# nicie_-_6.net
KiCad netlist of a schematic drawn in EAGLE
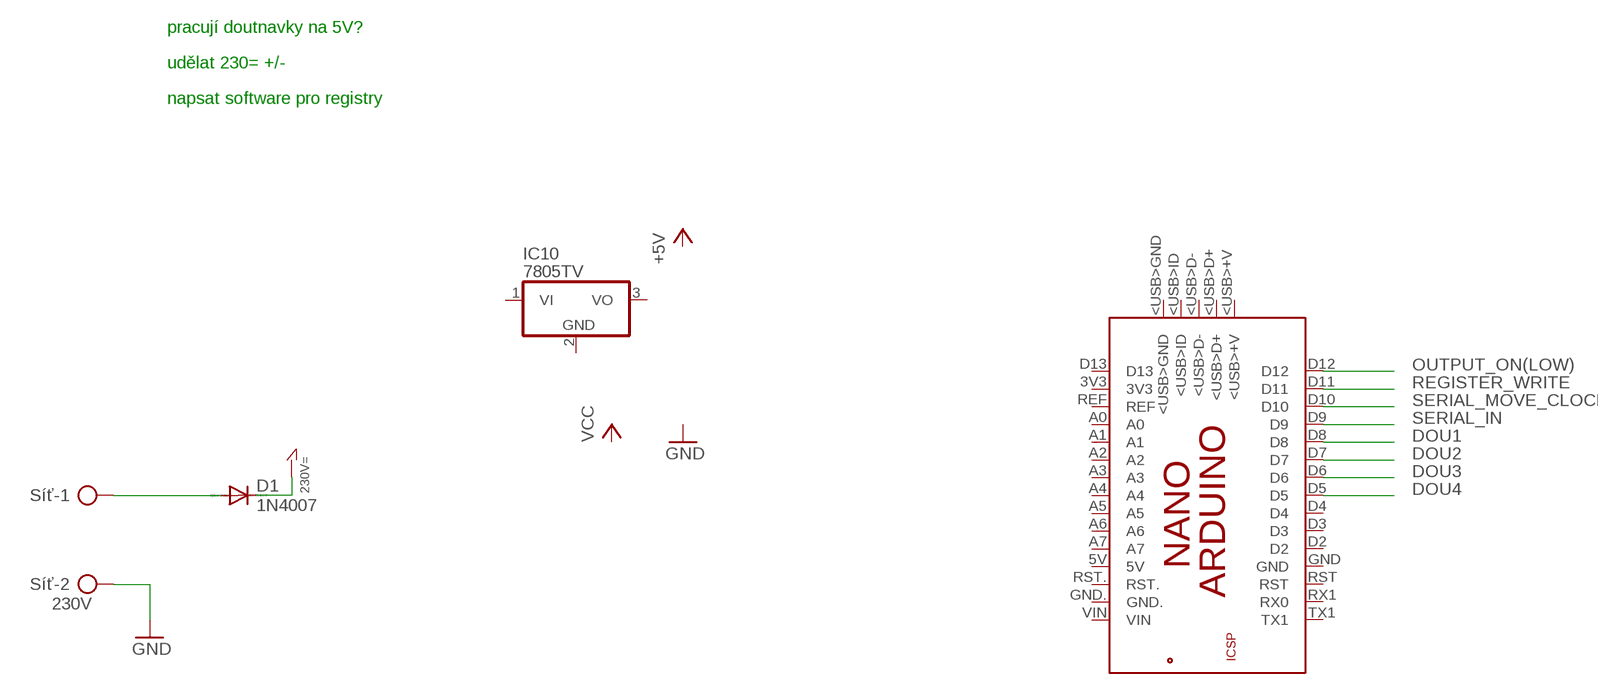
[diagram p0: schematic, sheet 1, part 1 of 2]
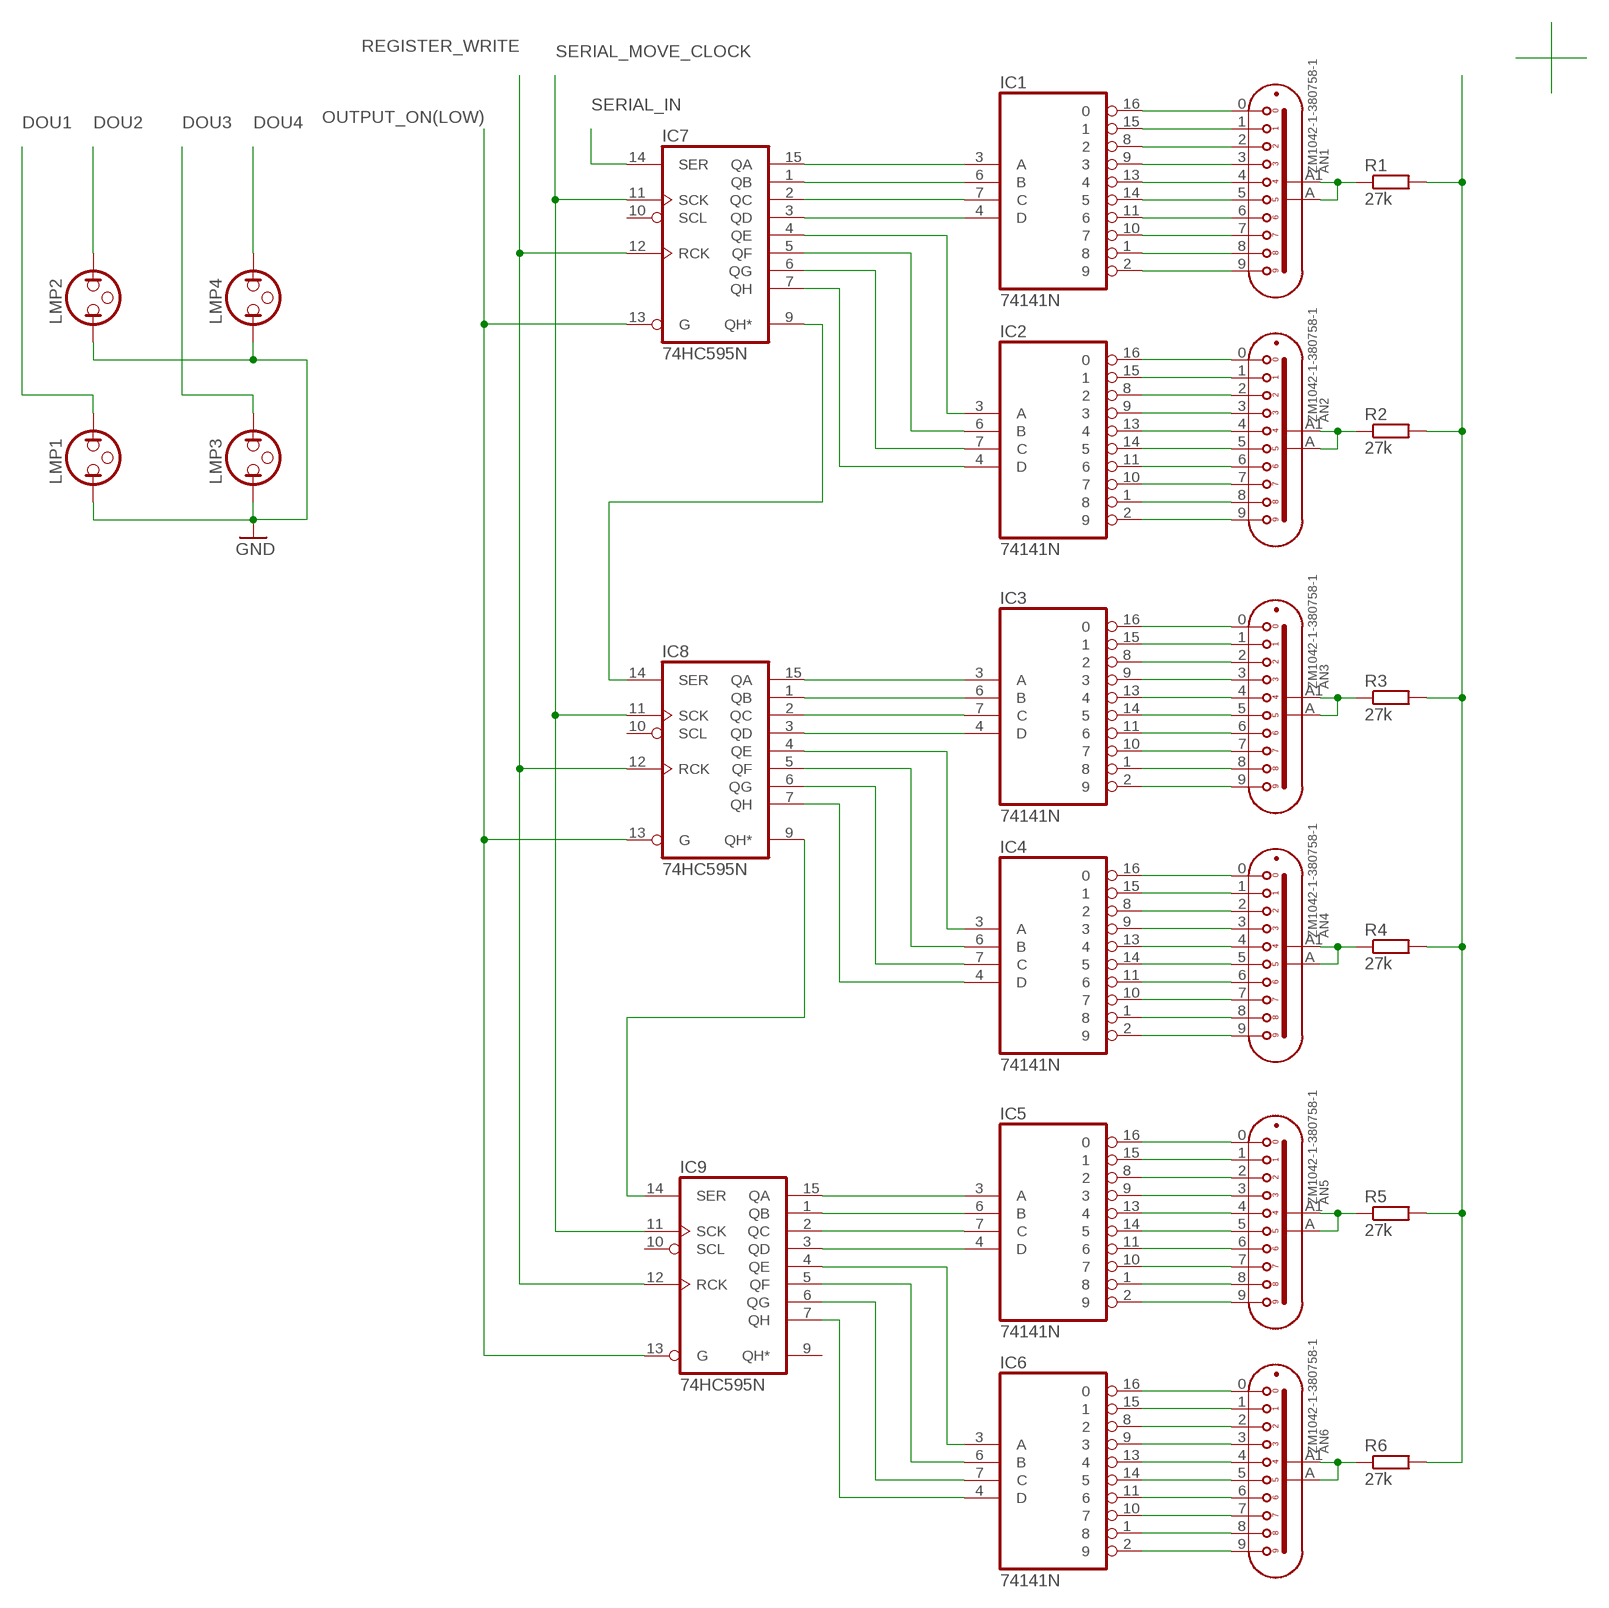
[diagram p1: schematic, sheet 1, part 2 of 2]

(export (version "E")
  (design (tool "Eeschema 10.0.6"))
  (components
    (comp (ref "AN1")
      (value "ZM1042-1-380758-1")
      (footprint "eagle-import:ZM1042-AMP")
      (libsource (lib "eagle-import") (part "ZM1042-1-380758-1"))
    )
    (comp (ref "AN2")
      (value "ZM1042-1-380758-1")
      (footprint "eagle-import:ZM1042-AMP")
      (libsource (lib "eagle-import") (part "ZM1042-1-380758-1"))
    )
    (comp (ref "AN3")
      (value "ZM1042-1-380758-1")
      (footprint "eagle-import:ZM1042-AMP")
      (libsource (lib "eagle-import") (part "ZM1042-1-380758-1"))
    )
    (comp (ref "AN4")
      (value "ZM1042-1-380758-1")
      (footprint "eagle-import:ZM1042-AMP")
      (libsource (lib "eagle-import") (part "ZM1042-1-380758-1"))
    )
    (comp (ref "AN5")
      (value "ZM1042-1-380758-1")
      (footprint "eagle-import:ZM1042-AMP")
      (libsource (lib "eagle-import") (part "ZM1042-1-380758-1"))
    )
    (comp (ref "AN6")
      (value "ZM1042-1-380758-1")
      (footprint "eagle-import:ZM1042-AMP")
      (libsource (lib "eagle-import") (part "ZM1042-1-380758-1"))
    )
    (comp (ref "D1")
      (value "1N4007")
      (footprint "eagle-import:DO41-10")
      (libsource (lib "eagle-import") (part "1N4004"))
    )
    (comp (ref "IC1")
      (value "74141N")
      (footprint "eagle-import:DIL16")
      (libsource (lib "eagle-import") (part "74141N"))
    )
    (comp (ref "IC2")
      (value "74141N")
      (footprint "eagle-import:DIL16")
      (libsource (lib "eagle-import") (part "74141N"))
    )
    (comp (ref "IC3")
      (value "74141N")
      (footprint "eagle-import:DIL16")
      (libsource (lib "eagle-import") (part "74141N"))
    )
    (comp (ref "IC4")
      (value "74141N")
      (footprint "eagle-import:DIL16")
      (libsource (lib "eagle-import") (part "74141N"))
    )
    (comp (ref "IC5")
      (value "74141N")
      (footprint "eagle-import:DIL16")
      (libsource (lib "eagle-import") (part "74141N"))
    )
    (comp (ref "IC6")
      (value "74141N")
      (footprint "eagle-import:DIL16")
      (libsource (lib "eagle-import") (part "74141N"))
    )
    (comp (ref "IC7")
      (value "74HC595N")
      (footprint "eagle-import:DIL16")
      (libsource (lib "eagle-import") (part "74595NHC"))
    )
    (comp (ref "IC8")
      (value "74HC595N")
      (footprint "eagle-import:DIL16")
      (libsource (lib "eagle-import") (part "74595NHC"))
    )
    (comp (ref "IC9")
      (value "74HC595N")
      (footprint "eagle-import:DIL16")
      (libsource (lib "eagle-import") (part "74595NHC"))
    )
    (comp (ref "IC10")
      (value "7805TV")
      (footprint "eagle-import:TO220V")
      (libsource (lib "eagle-import") (part "78TV05"))
    )
    (comp (ref "LMP1")
      (value "NEON")
      (footprint "eagle-import:LDH-3R")
      (libsource (lib "eagle-import") (part "NEON"))
    )
    (comp (ref "LMP2")
      (value "NEON")
      (footprint "eagle-import:LDH-3R")
      (libsource (lib "eagle-import") (part "NEON"))
    )
    (comp (ref "LMP3")
      (value "NEON")
      (footprint "eagle-import:LDH-3R")
      (libsource (lib "eagle-import") (part "NEON"))
    )
    (comp (ref "LMP4")
      (value "NEON")
      (footprint "eagle-import:LDH-3R")
      (libsource (lib "eagle-import") (part "NEON"))
    )
    (comp (ref "PCB1")
      (value "ARDUINO_NANO")
      (footprint "eagle-import:ARDUINO_NANO")
      (libsource (lib "eagle-import") (part "ARDUINO_NANO"))
    )
    (comp (ref "R1")
      (value "27k")
      (footprint "eagle-import:0309_12")
      (libsource (lib "eagle-import") (part "R-EU_0309/12"))
    )
    (comp (ref "R2")
      (value "27k")
      (footprint "eagle-import:0309_12")
      (libsource (lib "eagle-import") (part "R-EU_0309/12"))
    )
    (comp (ref "R3")
      (value "27k")
      (footprint "eagle-import:0309_12")
      (libsource (lib "eagle-import") (part "R-EU_0309/12"))
    )
    (comp (ref "R4")
      (value "27k")
      (footprint "eagle-import:0309_12")
      (libsource (lib "eagle-import") (part "R-EU_0309/12"))
    )
    (comp (ref "R5")
      (value "27k")
      (footprint "eagle-import:0309_12")
      (libsource (lib "eagle-import") (part "R-EU_0309/12"))
    )
    (comp (ref "R6")
      (value "27k")
      (footprint "eagle-import:0309_12")
      (libsource (lib "eagle-import") (part "R-EU_0309/12"))
    )
    (comp (ref "Síť")
      (value "230V")
      (footprint "eagle-import:AK500_2")
      (libsource (lib "eagle-import") (part "AK500/2"))
    )
  )
  (nets
    (net (code "2") (name "/DOU1") (class "Default")
      (node (ref "LMP1") (pin "2") (pinfunction "2_2") (pintype "passive"))
      (node (ref "PCB1") (pin "D8") (pinfunction "D8_D8") (pintype "bidirectional"))
    )
    (net (code "3") (name "/DOU2") (class "Default")
      (node (ref "LMP2") (pin "2") (pinfunction "2_2") (pintype "passive"))
      (node (ref "PCB1") (pin "D7") (pinfunction "D7_D7") (pintype "bidirectional"))
    )
    (net (code "4") (name "/DOU3") (class "Default")
      (node (ref "LMP3") (pin "2") (pinfunction "2_2") (pintype "passive"))
      (node (ref "PCB1") (pin "D6") (pinfunction "D6_D6") (pintype "bidirectional"))
    )
    (net (code "5") (name "/DOU4") (class "Default")
      (node (ref "LMP4") (pin "2") (pinfunction "2_2") (pintype "passive"))
      (node (ref "PCB1") (pin "D5") (pinfunction "D5_D5") (pintype "bidirectional"))
    )
    (net (code "6") (name "/OUTPUT_ON(LOW)") (class "Default")
      (node (ref "IC7") (pin "13") (pinfunction "G_13") (pintype "input"))
      (node (ref "IC8") (pin "13") (pinfunction "G_13") (pintype "input"))
      (node (ref "IC9") (pin "13") (pinfunction "G_13") (pintype "input"))
      (node (ref "PCB1") (pin "D12") (pinfunction "D12_D12") (pintype "bidirectional"))
    )
    (net (code "7") (name "/REGISTER_WRITE") (class "Default")
      (node (ref "IC7") (pin "12") (pinfunction "RCK_12") (pintype "input"))
      (node (ref "IC8") (pin "12") (pinfunction "RCK_12") (pintype "input"))
      (node (ref "IC9") (pin "12") (pinfunction "RCK_12") (pintype "input"))
      (node (ref "PCB1") (pin "D11") (pinfunction "D11_D11") (pintype "bidirectional"))
    )
    (net (code "8") (name "/SERIAL_IN") (class "Default")
      (node (ref "IC7") (pin "14") (pinfunction "SER_14") (pintype "input"))
      (node (ref "PCB1") (pin "D9") (pinfunction "D9_D9") (pintype "bidirectional"))
    )
    (net (code "9") (name "/SERIAL_MOVE_CLOCK") (class "Default")
      (node (ref "IC7") (pin "11") (pinfunction "SCK_11") (pintype "input"))
      (node (ref "IC8") (pin "11") (pinfunction "SCK_11") (pintype "input"))
      (node (ref "IC9") (pin "11") (pinfunction "SCK_11") (pintype "input"))
      (node (ref "PCB1") (pin "D10") (pinfunction "D10_D10") (pintype "bidirectional"))
    )
    (net (code "10") (name "230V=") (class "Default")
      (node (ref "D1") (pin "C") (pinfunction "C_C") (pintype "passive"))
    )
    (net (code "11") (name "GND") (class "Default")
      (node (ref "LMP1") (pin "1") (pinfunction "1_1") (pintype "passive"))
      (node (ref "LMP2") (pin "1") (pinfunction "1_1") (pintype "passive"))
      (node (ref "LMP3") (pin "1") (pinfunction "1_1") (pintype "passive"))
      (node (ref "LMP4") (pin "1") (pinfunction "1_1") (pintype "passive"))
      (node (ref "Síť") (pin "2") (pinfunction "KL_2") (pintype "passive"))
    )
    (net (code "12") (name "Net-(AN1-A1)") (class "Default")
      (node (ref "AN1") (pin "A") (pinfunction "A1_A") (pintype "passive"))
      (node (ref "AN1") (pin "A1") (pinfunction "A2_A1") (pintype "passive"))
      (node (ref "R1") (pin "1") (pinfunction "1_1") (pintype "passive"))
    )
    (net (code "13") (name "Net-(AN2-A1)") (class "Default")
      (node (ref "AN2") (pin "A") (pinfunction "A1_A") (pintype "passive"))
      (node (ref "AN2") (pin "A1") (pinfunction "A2_A1") (pintype "passive"))
      (node (ref "R2") (pin "1") (pinfunction "1_1") (pintype "passive"))
    )
    (net (code "14") (name "Net-(AN3-A1)") (class "Default")
      (node (ref "AN3") (pin "A") (pinfunction "A1_A") (pintype "passive"))
      (node (ref "AN3") (pin "A1") (pinfunction "A2_A1") (pintype "passive"))
      (node (ref "R3") (pin "1") (pinfunction "1_1") (pintype "passive"))
    )
    (net (code "15") (name "Net-(AN4-A1)") (class "Default")
      (node (ref "AN4") (pin "A") (pinfunction "A1_A") (pintype "passive"))
      (node (ref "AN4") (pin "A1") (pinfunction "A2_A1") (pintype "passive"))
      (node (ref "R4") (pin "1") (pinfunction "1_1") (pintype "passive"))
    )
    (net (code "16") (name "Net-(AN5-A1)") (class "Default")
      (node (ref "AN5") (pin "A") (pinfunction "A1_A") (pintype "passive"))
      (node (ref "AN5") (pin "A1") (pinfunction "A2_A1") (pintype "passive"))
      (node (ref "R5") (pin "1") (pinfunction "1_1") (pintype "passive"))
    )
    (net (code "17") (name "Net-(AN6-A1)") (class "Default")
      (node (ref "AN6") (pin "A") (pinfunction "A1_A") (pintype "passive"))
      (node (ref "AN6") (pin "A1") (pinfunction "A2_A1") (pintype "passive"))
      (node (ref "R6") (pin "1") (pinfunction "1_1") (pintype "passive"))
    )
    (net (code "18") (name "Net-(IC1A-0)") (class "Default")
      (node (ref "AN1") (pin "0") (pinfunction "0_0") (pintype "passive"))
      (node (ref "IC1") (pin "16") (pinfunction "0_16") (pintype "open_collector"))
    )
    (net (code "19") (name "Net-(IC1A-1)") (class "Default")
      (node (ref "AN1") (pin "1") (pinfunction "1_1") (pintype "passive"))
      (node (ref "IC1") (pin "15") (pinfunction "1_15") (pintype "open_collector"))
    )
    (net (code "20") (name "Net-(IC1A-2)") (class "Default")
      (node (ref "AN1") (pin "2") (pinfunction "2_2") (pintype "passive"))
      (node (ref "IC1") (pin "8") (pinfunction "2_8") (pintype "open_collector"))
    )
    (net (code "21") (name "Net-(IC1A-3)") (class "Default")
      (node (ref "AN1") (pin "3") (pinfunction "3_3") (pintype "passive"))
      (node (ref "IC1") (pin "9") (pinfunction "3_9") (pintype "open_collector"))
    )
    (net (code "22") (name "Net-(IC1A-4)") (class "Default")
      (node (ref "AN1") (pin "4") (pinfunction "4_4") (pintype "passive"))
      (node (ref "IC1") (pin "13") (pinfunction "4_13") (pintype "open_collector"))
    )
    (net (code "23") (name "Net-(IC1A-5)") (class "Default")
      (node (ref "AN1") (pin "5") (pinfunction "5_5") (pintype "passive"))
      (node (ref "IC1") (pin "14") (pinfunction "5_14") (pintype "open_collector"))
    )
    (net (code "24") (name "Net-(IC1A-6)") (class "Default")
      (node (ref "AN1") (pin "6") (pinfunction "6_6") (pintype "passive"))
      (node (ref "IC1") (pin "11") (pinfunction "6_11") (pintype "open_collector"))
    )
    (net (code "25") (name "Net-(IC1A-7)") (class "Default")
      (node (ref "AN1") (pin "7") (pinfunction "7_7") (pintype "passive"))
      (node (ref "IC1") (pin "10") (pinfunction "7_10") (pintype "open_collector"))
    )
    (net (code "26") (name "Net-(IC1A-8)") (class "Default")
      (node (ref "AN1") (pin "8") (pinfunction "8_8") (pintype "passive"))
      (node (ref "IC1") (pin "1") (pinfunction "8_1") (pintype "open_collector"))
    )
    (net (code "27") (name "Net-(IC1A-9)") (class "Default")
      (node (ref "AN1") (pin "9") (pinfunction "9_9") (pintype "passive"))
      (node (ref "IC1") (pin "2") (pinfunction "9_2") (pintype "open_collector"))
    )
    (net (code "28") (name "Net-(IC1A-A)") (class "Default")
      (node (ref "IC1") (pin "3") (pinfunction "A_3") (pintype "input"))
      (node (ref "IC7") (pin "15") (pinfunction "QA_15") (pintype "tri_state"))
    )
    (net (code "29") (name "Net-(IC1A-B)") (class "Default")
      (node (ref "IC1") (pin "6") (pinfunction "B_6") (pintype "input"))
      (node (ref "IC7") (pin "1") (pinfunction "QB_1") (pintype "tri_state"))
    )
    (net (code "30") (name "Net-(IC1A-C)") (class "Default")
      (node (ref "IC1") (pin "7") (pinfunction "C_7") (pintype "input"))
      (node (ref "IC7") (pin "2") (pinfunction "QC_2") (pintype "tri_state"))
    )
    (net (code "31") (name "Net-(IC1A-D)") (class "Default")
      (node (ref "IC1") (pin "4") (pinfunction "D_4") (pintype "input"))
      (node (ref "IC7") (pin "3") (pinfunction "QD_3") (pintype "tri_state"))
    )
    (net (code "32") (name "Net-(IC2A-0)") (class "Default")
      (node (ref "AN2") (pin "0") (pinfunction "0_0") (pintype "passive"))
      (node (ref "IC2") (pin "16") (pinfunction "0_16") (pintype "open_collector"))
    )
    (net (code "33") (name "Net-(IC2A-1)") (class "Default")
      (node (ref "AN2") (pin "1") (pinfunction "1_1") (pintype "passive"))
      (node (ref "IC2") (pin "15") (pinfunction "1_15") (pintype "open_collector"))
    )
    (net (code "34") (name "Net-(IC2A-2)") (class "Default")
      (node (ref "AN2") (pin "2") (pinfunction "2_2") (pintype "passive"))
      (node (ref "IC2") (pin "8") (pinfunction "2_8") (pintype "open_collector"))
    )
    (net (code "35") (name "Net-(IC2A-3)") (class "Default")
      (node (ref "AN2") (pin "3") (pinfunction "3_3") (pintype "passive"))
      (node (ref "IC2") (pin "9") (pinfunction "3_9") (pintype "open_collector"))
    )
    (net (code "36") (name "Net-(IC2A-4)") (class "Default")
      (node (ref "AN2") (pin "4") (pinfunction "4_4") (pintype "passive"))
      (node (ref "IC2") (pin "13") (pinfunction "4_13") (pintype "open_collector"))
    )
    (net (code "37") (name "Net-(IC2A-5)") (class "Default")
      (node (ref "AN2") (pin "5") (pinfunction "5_5") (pintype "passive"))
      (node (ref "IC2") (pin "14") (pinfunction "5_14") (pintype "open_collector"))
    )
    (net (code "38") (name "Net-(IC2A-6)") (class "Default")
      (node (ref "AN2") (pin "6") (pinfunction "6_6") (pintype "passive"))
      (node (ref "IC2") (pin "11") (pinfunction "6_11") (pintype "open_collector"))
    )
    (net (code "39") (name "Net-(IC2A-7)") (class "Default")
      (node (ref "AN2") (pin "7") (pinfunction "7_7") (pintype "passive"))
      (node (ref "IC2") (pin "10") (pinfunction "7_10") (pintype "open_collector"))
    )
    (net (code "40") (name "Net-(IC2A-8)") (class "Default")
      (node (ref "AN2") (pin "8") (pinfunction "8_8") (pintype "passive"))
      (node (ref "IC2") (pin "1") (pinfunction "8_1") (pintype "open_collector"))
    )
    (net (code "41") (name "Net-(IC2A-9)") (class "Default")
      (node (ref "AN2") (pin "9") (pinfunction "9_9") (pintype "passive"))
      (node (ref "IC2") (pin "2") (pinfunction "9_2") (pintype "open_collector"))
    )
    (net (code "42") (name "Net-(IC2A-A)") (class "Default")
      (node (ref "IC2") (pin "3") (pinfunction "A_3") (pintype "input"))
      (node (ref "IC7") (pin "4") (pinfunction "QE_4") (pintype "tri_state"))
    )
    (net (code "43") (name "Net-(IC2A-B)") (class "Default")
      (node (ref "IC2") (pin "6") (pinfunction "B_6") (pintype "input"))
      (node (ref "IC7") (pin "5") (pinfunction "QF_5") (pintype "tri_state"))
    )
    (net (code "44") (name "Net-(IC2A-C)") (class "Default")
      (node (ref "IC2") (pin "7") (pinfunction "C_7") (pintype "input"))
      (node (ref "IC7") (pin "6") (pinfunction "QG_6") (pintype "tri_state"))
    )
    (net (code "45") (name "Net-(IC2A-D)") (class "Default")
      (node (ref "IC2") (pin "4") (pinfunction "D_4") (pintype "input"))
      (node (ref "IC7") (pin "7") (pinfunction "QH_7") (pintype "tri_state"))
    )
    (net (code "46") (name "Net-(IC3A-0)") (class "Default")
      (node (ref "AN3") (pin "0") (pinfunction "0_0") (pintype "passive"))
      (node (ref "IC3") (pin "16") (pinfunction "0_16") (pintype "open_collector"))
    )
    (net (code "47") (name "Net-(IC3A-1)") (class "Default")
      (node (ref "AN3") (pin "1") (pinfunction "1_1") (pintype "passive"))
      (node (ref "IC3") (pin "15") (pinfunction "1_15") (pintype "open_collector"))
    )
    (net (code "48") (name "Net-(IC3A-2)") (class "Default")
      (node (ref "AN3") (pin "2") (pinfunction "2_2") (pintype "passive"))
      (node (ref "IC3") (pin "8") (pinfunction "2_8") (pintype "open_collector"))
    )
    (net (code "49") (name "Net-(IC3A-3)") (class "Default")
      (node (ref "AN3") (pin "3") (pinfunction "3_3") (pintype "passive"))
      (node (ref "IC3") (pin "9") (pinfunction "3_9") (pintype "open_collector"))
    )
    (net (code "50") (name "Net-(IC3A-4)") (class "Default")
      (node (ref "AN3") (pin "4") (pinfunction "4_4") (pintype "passive"))
      (node (ref "IC3") (pin "13") (pinfunction "4_13") (pintype "open_collector"))
    )
    (net (code "51") (name "Net-(IC3A-5)") (class "Default")
      (node (ref "AN3") (pin "5") (pinfunction "5_5") (pintype "passive"))
      (node (ref "IC3") (pin "14") (pinfunction "5_14") (pintype "open_collector"))
    )
    (net (code "52") (name "Net-(IC3A-6)") (class "Default")
      (node (ref "AN3") (pin "6") (pinfunction "6_6") (pintype "passive"))
      (node (ref "IC3") (pin "11") (pinfunction "6_11") (pintype "open_collector"))
    )
    (net (code "53") (name "Net-(IC3A-7)") (class "Default")
      (node (ref "AN3") (pin "7") (pinfunction "7_7") (pintype "passive"))
      (node (ref "IC3") (pin "10") (pinfunction "7_10") (pintype "open_collector"))
    )
    (net (code "54") (name "Net-(IC3A-8)") (class "Default")
      (node (ref "AN3") (pin "8") (pinfunction "8_8") (pintype "passive"))
      (node (ref "IC3") (pin "1") (pinfunction "8_1") (pintype "open_collector"))
    )
    (net (code "55") (name "Net-(IC3A-9)") (class "Default")
      (node (ref "AN3") (pin "9") (pinfunction "9_9") (pintype "passive"))
      (node (ref "IC3") (pin "2") (pinfunction "9_2") (pintype "open_collector"))
    )
    (net (code "56") (name "Net-(IC3A-A)") (class "Default")
      (node (ref "IC3") (pin "3") (pinfunction "A_3") (pintype "input"))
      (node (ref "IC8") (pin "15") (pinfunction "QA_15") (pintype "tri_state"))
    )
    (net (code "57") (name "Net-(IC3A-B)") (class "Default")
      (node (ref "IC3") (pin "6") (pinfunction "B_6") (pintype "input"))
      (node (ref "IC8") (pin "1") (pinfunction "QB_1") (pintype "tri_state"))
    )
    (net (code "58") (name "Net-(IC3A-C)") (class "Default")
      (node (ref "IC3") (pin "7") (pinfunction "C_7") (pintype "input"))
      (node (ref "IC8") (pin "2") (pinfunction "QC_2") (pintype "tri_state"))
    )
    (net (code "59") (name "Net-(IC3A-D)") (class "Default")
      (node (ref "IC3") (pin "4") (pinfunction "D_4") (pintype "input"))
      (node (ref "IC8") (pin "3") (pinfunction "QD_3") (pintype "tri_state"))
    )
    (net (code "60") (name "Net-(IC4A-0)") (class "Default")
      (node (ref "AN4") (pin "0") (pinfunction "0_0") (pintype "passive"))
      (node (ref "IC4") (pin "16") (pinfunction "0_16") (pintype "open_collector"))
    )
    (net (code "61") (name "Net-(IC4A-1)") (class "Default")
      (node (ref "AN4") (pin "1") (pinfunction "1_1") (pintype "passive"))
      (node (ref "IC4") (pin "15") (pinfunction "1_15") (pintype "open_collector"))
    )
    (net (code "62") (name "Net-(IC4A-2)") (class "Default")
      (node (ref "AN4") (pin "2") (pinfunction "2_2") (pintype "passive"))
      (node (ref "IC4") (pin "8") (pinfunction "2_8") (pintype "open_collector"))
    )
    (net (code "63") (name "Net-(IC4A-3)") (class "Default")
      (node (ref "AN4") (pin "3") (pinfunction "3_3") (pintype "passive"))
      (node (ref "IC4") (pin "9") (pinfunction "3_9") (pintype "open_collector"))
    )
    (net (code "64") (name "Net-(IC4A-4)") (class "Default")
      (node (ref "AN4") (pin "4") (pinfunction "4_4") (pintype "passive"))
      (node (ref "IC4") (pin "13") (pinfunction "4_13") (pintype "open_collector"))
    )
    (net (code "65") (name "Net-(IC4A-5)") (class "Default")
      (node (ref "AN4") (pin "5") (pinfunction "5_5") (pintype "passive"))
      (node (ref "IC4") (pin "14") (pinfunction "5_14") (pintype "open_collector"))
    )
    (net (code "66") (name "Net-(IC4A-6)") (class "Default")
      (node (ref "AN4") (pin "6") (pinfunction "6_6") (pintype "passive"))
      (node (ref "IC4") (pin "11") (pinfunction "6_11") (pintype "open_collector"))
    )
    (net (code "67") (name "Net-(IC4A-7)") (class "Default")
      (node (ref "AN4") (pin "7") (pinfunction "7_7") (pintype "passive"))
      (node (ref "IC4") (pin "10") (pinfunction "7_10") (pintype "open_collector"))
    )
    (net (code "68") (name "Net-(IC4A-8)") (class "Default")
      (node (ref "AN4") (pin "8") (pinfunction "8_8") (pintype "passive"))
      (node (ref "IC4") (pin "1") (pinfunction "8_1") (pintype "open_collector"))
    )
    (net (code "69") (name "Net-(IC4A-9)") (class "Default")
      (node (ref "AN4") (pin "9") (pinfunction "9_9") (pintype "passive"))
      (node (ref "IC4") (pin "2") (pinfunction "9_2") (pintype "open_collector"))
    )
    (net (code "70") (name "Net-(IC4A-A)") (class "Default")
      (node (ref "IC4") (pin "3") (pinfunction "A_3") (pintype "input"))
      (node (ref "IC8") (pin "4") (pinfunction "QE_4") (pintype "tri_state"))
    )
    (net (code "71") (name "Net-(IC4A-B)") (class "Default")
      (node (ref "IC4") (pin "6") (pinfunction "B_6") (pintype "input"))
      (node (ref "IC8") (pin "5") (pinfunction "QF_5") (pintype "tri_state"))
    )
    (net (code "72") (name "Net-(IC4A-C)") (class "Default")
      (node (ref "IC4") (pin "7") (pinfunction "C_7") (pintype "input"))
      (node (ref "IC8") (pin "6") (pinfunction "QG_6") (pintype "tri_state"))
    )
    (net (code "73") (name "Net-(IC4A-D)") (class "Default")
      (node (ref "IC4") (pin "4") (pinfunction "D_4") (pintype "input"))
      (node (ref "IC8") (pin "7") (pinfunction "QH_7") (pintype "tri_state"))
    )
    (net (code "74") (name "Net-(IC5A-0)") (class "Default")
      (node (ref "AN5") (pin "0") (pinfunction "0_0") (pintype "passive"))
      (node (ref "IC5") (pin "16") (pinfunction "0_16") (pintype "open_collector"))
    )
    (net (code "75") (name "Net-(IC5A-1)") (class "Default")
      (node (ref "AN5") (pin "1") (pinfunction "1_1") (pintype "passive"))
      (node (ref "IC5") (pin "15") (pinfunction "1_15") (pintype "open_collector"))
    )
    (net (code "76") (name "Net-(IC5A-2)") (class "Default")
      (node (ref "AN5") (pin "2") (pinfunction "2_2") (pintype "passive"))
      (node (ref "IC5") (pin "8") (pinfunction "2_8") (pintype "open_collector"))
    )
    (net (code "77") (name "Net-(IC5A-3)") (class "Default")
      (node (ref "AN5") (pin "3") (pinfunction "3_3") (pintype "passive"))
      (node (ref "IC5") (pin "9") (pinfunction "3_9") (pintype "open_collector"))
    )
    (net (code "78") (name "Net-(IC5A-4)") (class "Default")
      (node (ref "AN5") (pin "4") (pinfunction "4_4") (pintype "passive"))
      (node (ref "IC5") (pin "13") (pinfunction "4_13") (pintype "open_collector"))
    )
    (net (code "79") (name "Net-(IC5A-5)") (class "Default")
      (node (ref "AN5") (pin "5") (pinfunction "5_5") (pintype "passive"))
      (node (ref "IC5") (pin "14") (pinfunction "5_14") (pintype "open_collector"))
    )
    (net (code "80") (name "Net-(IC5A-6)") (class "Default")
      (node (ref "AN5") (pin "6") (pinfunction "6_6") (pintype "passive"))
      (node (ref "IC5") (pin "11") (pinfunction "6_11") (pintype "open_collector"))
    )
    (net (code "81") (name "Net-(IC5A-7)") (class "Default")
      (node (ref "AN5") (pin "7") (pinfunction "7_7") (pintype "passive"))
      (node (ref "IC5") (pin "10") (pinfunction "7_10") (pintype "open_collector"))
    )
    (net (code "82") (name "Net-(IC5A-8)") (class "Default")
      (node (ref "AN5") (pin "8") (pinfunction "8_8") (pintype "passive"))
      (node (ref "IC5") (pin "1") (pinfunction "8_1") (pintype "open_collector"))
    )
    (net (code "83") (name "Net-(IC5A-9)") (class "Default")
      (node (ref "AN5") (pin "9") (pinfunction "9_9") (pintype "passive"))
      (node (ref "IC5") (pin "2") (pinfunction "9_2") (pintype "open_collector"))
    )
    (net (code "84") (name "Net-(IC5A-A)") (class "Default")
      (node (ref "IC5") (pin "3") (pinfunction "A_3") (pintype "input"))
      (node (ref "IC9") (pin "15") (pinfunction "QA_15") (pintype "tri_state"))
    )
    (net (code "85") (name "Net-(IC5A-B)") (class "Default")
      (node (ref "IC5") (pin "6") (pinfunction "B_6") (pintype "input"))
      (node (ref "IC9") (pin "1") (pinfunction "QB_1") (pintype "tri_state"))
    )
    (net (code "86") (name "Net-(IC5A-C)") (class "Default")
      (node (ref "IC5") (pin "7") (pinfunction "C_7") (pintype "input"))
      (node (ref "IC9") (pin "2") (pinfunction "QC_2") (pintype "tri_state"))
    )
    (net (code "87") (name "Net-(IC5A-D)") (class "Default")
      (node (ref "IC5") (pin "4") (pinfunction "D_4") (pintype "input"))
      (node (ref "IC9") (pin "3") (pinfunction "QD_3") (pintype "tri_state"))
    )
    (net (code "88") (name "Net-(IC6A-0)") (class "Default")
      (node (ref "AN6") (pin "0") (pinfunction "0_0") (pintype "passive"))
      (node (ref "IC6") (pin "16") (pinfunction "0_16") (pintype "open_collector"))
    )
    (net (code "89") (name "Net-(IC6A-1)") (class "Default")
      (node (ref "AN6") (pin "1") (pinfunction "1_1") (pintype "passive"))
      (node (ref "IC6") (pin "15") (pinfunction "1_15") (pintype "open_collector"))
    )
    (net (code "90") (name "Net-(IC6A-2)") (class "Default")
      (node (ref "AN6") (pin "2") (pinfunction "2_2") (pintype "passive"))
      (node (ref "IC6") (pin "8") (pinfunction "2_8") (pintype "open_collector"))
    )
    (net (code "91") (name "Net-(IC6A-3)") (class "Default")
      (node (ref "AN6") (pin "3") (pinfunction "3_3") (pintype "passive"))
      (node (ref "IC6") (pin "9") (pinfunction "3_9") (pintype "open_collector"))
    )
    (net (code "92") (name "Net-(IC6A-4)") (class "Default")
      (node (ref "AN6") (pin "4") (pinfunction "4_4") (pintype "passive"))
      (node (ref "IC6") (pin "13") (pinfunction "4_13") (pintype "open_collector"))
    )
    (net (code "93") (name "Net-(IC6A-5)") (class "Default")
      (node (ref "AN6") (pin "5") (pinfunction "5_5") (pintype "passive"))
      (node (ref "IC6") (pin "14") (pinfunction "5_14") (pintype "open_collector"))
    )
    (net (code "94") (name "Net-(IC6A-6)") (class "Default")
      (node (ref "AN6") (pin "6") (pinfunction "6_6") (pintype "passive"))
      (node (ref "IC6") (pin "11") (pinfunction "6_11") (pintype "open_collector"))
    )
    (net (code "95") (name "Net-(IC6A-7)") (class "Default")
      (node (ref "AN6") (pin "7") (pinfunction "7_7") (pintype "passive"))
      (node (ref "IC6") (pin "10") (pinfunction "7_10") (pintype "open_collector"))
    )
    (net (code "96") (name "Net-(IC6A-8)") (class "Default")
      (node (ref "AN6") (pin "8") (pinfunction "8_8") (pintype "passive"))
      (node (ref "IC6") (pin "1") (pinfunction "8_1") (pintype "open_collector"))
    )
    (net (code "97") (name "Net-(IC6A-9)") (class "Default")
      (node (ref "AN6") (pin "9") (pinfunction "9_9") (pintype "passive"))
      (node (ref "IC6") (pin "2") (pinfunction "9_2") (pintype "open_collector"))
    )
    (net (code "98") (name "Net-(IC6A-A)") (class "Default")
      (node (ref "IC6") (pin "3") (pinfunction "A_3") (pintype "input"))
      (node (ref "IC9") (pin "4") (pinfunction "QE_4") (pintype "tri_state"))
    )
    (net (code "99") (name "Net-(IC6A-B)") (class "Default")
      (node (ref "IC6") (pin "6") (pinfunction "B_6") (pintype "input"))
      (node (ref "IC9") (pin "5") (pinfunction "QF_5") (pintype "tri_state"))
    )
    (net (code "100") (name "Net-(IC6A-C)") (class "Default")
      (node (ref "IC6") (pin "7") (pinfunction "C_7") (pintype "input"))
      (node (ref "IC9") (pin "6") (pinfunction "QG_6") (pintype "tri_state"))
    )
    (net (code "101") (name "Net-(IC6A-D)") (class "Default")
      (node (ref "IC6") (pin "4") (pinfunction "D_4") (pintype "input"))
      (node (ref "IC9") (pin "7") (pinfunction "QH_7") (pintype "tri_state"))
    )
    (net (code "102") (name "Net-(IC7A-QH*)") (class "Default")
      (node (ref "IC7") (pin "9") (pinfunction "QH*_9") (pintype "tri_state"))
      (node (ref "IC8") (pin "14") (pinfunction "SER_14") (pintype "input"))
    )
    (net (code "103") (name "Net-(IC8A-QH*)") (class "Default")
      (node (ref "IC8") (pin "9") (pinfunction "QH*_9") (pintype "tri_state"))
      (node (ref "IC9") (pin "14") (pinfunction "SER_14") (pintype "input"))
    )
    (net (code "104") (name "Net-(R1-Pad2)") (class "Default")
      (node (ref "R1") (pin "2") (pinfunction "2_2") (pintype "passive"))
      (node (ref "R2") (pin "2") (pinfunction "2_2") (pintype "passive"))
      (node (ref "R3") (pin "2") (pinfunction "2_2") (pintype "passive"))
      (node (ref "R4") (pin "2") (pinfunction "2_2") (pintype "passive"))
      (node (ref "R5") (pin "2") (pinfunction "2_2") (pintype "passive"))
      (node (ref "R6") (pin "2") (pinfunction "2_2") (pintype "passive"))
    )
    (net (code "105") (name "Net-(SíťA-KL)") (class "Default")
      (node (ref "D1") (pin "A") (pinfunction "A_A") (pintype "passive"))
      (node (ref "Síť") (pin "1") (pinfunction "KL_1") (pintype "passive"))
    )
    (net (code "107") (name "unconnected-(IC7A-SCL-Pad10)") (class "Default")
      (node (ref "IC7") (pin "10") (pinfunction "SCL_10") (pintype "input"))
    )
    (net (code "108") (name "unconnected-(IC8A-SCL-Pad10)") (class "Default")
      (node (ref "IC8") (pin "10") (pinfunction "SCL_10") (pintype "input"))
    )
    (net (code "109") (name "unconnected-(IC9A-QH*-Pad9)") (class "Default")
      (node (ref "IC9") (pin "9") (pinfunction "QH*_9") (pintype "tri_state"))
    )
    (net (code "110") (name "unconnected-(IC9A-SCL-Pad10)") (class "Default")
      (node (ref "IC9") (pin "10") (pinfunction "SCL_10") (pintype "input"))
    )
    (net (code "111") (name "unconnected-(IC10-GND-Pad2)") (class "Default")
      (node (ref "IC10") (pin "2") (pinfunction "GND_2") (pintype "passive"))
    )
    (net (code "112") (name "unconnected-(IC10-VI-Pad1)") (class "Default")
      (node (ref "IC10") (pin "1") (pinfunction "VI_1") (pintype "input"))
    )
    (net (code "113") (name "unconnected-(IC10-VO-Pad3)") (class "Default")
      (node (ref "IC10") (pin "3") (pinfunction "VO_3") (pintype "passive"))
    )
    (net (code "114") (name "unconnected-(PCB1-Pad3V3)") (class "Default")
      (node (ref "PCB1") (pin "3V3") (pinfunction "3V3_3V3") (pintype "bidirectional"))
    )
    (net (code "115") (name "unconnected-(PCB1-Pad5V)") (class "Default")
      (node (ref "PCB1") (pin "5V") (pinfunction "5V_5V") (pintype "bidirectional"))
    )
    (net (code "116") (name "unconnected-(PCB1-Pad5V.)") (class "Default")
      (node (ref "PCB1") (pin "5V.") (pinfunction "5V._5V.") (pintype "bidirectional"))
    )
    (net (code "117") (name "unconnected-(PCB1-Pad<USB>+V)") (class "Default")
      (node (ref "PCB1") (pin "<USB>+V") (pinfunction "<USB>+V_<USB>+V") (pintype "bidirectional"))
    )
    (net (code "118") (name "unconnected-(PCB1-Pad<USB>D+)") (class "Default")
      (node (ref "PCB1") (pin "<USB>D+") (pinfunction "<USB>D+_<USB>D+") (pintype "bidirectional"))
    )
    (net (code "119") (name "unconnected-(PCB1-Pad<USB>D-)") (class "Default")
      (node (ref "PCB1") (pin "<USB>D-") (pinfunction "<USB>D-_<USB>D-") (pintype "bidirectional"))
    )
    (net (code "120") (name "unconnected-(PCB1-Pad<USB>GND)") (class "Default")
      (node (ref "PCB1") (pin "<USB>GND") (pinfunction "<USB>GND_<USB>GND") (pintype "bidirectional"))
    )
    (net (code "121") (name "unconnected-(PCB1-Pad<USB>ID)") (class "Default")
      (node (ref "PCB1") (pin "<USB>ID") (pinfunction "<USB>ID_<USB>ID") (pintype "bidirectional"))
    )
    (net (code "122") (name "unconnected-(PCB1-PadA0)") (class "Default")
      (node (ref "PCB1") (pin "A0") (pinfunction "A0_A0") (pintype "bidirectional"))
    )
    (net (code "123") (name "unconnected-(PCB1-PadA1)") (class "Default")
      (node (ref "PCB1") (pin "A1") (pinfunction "A1_A1") (pintype "bidirectional"))
    )
    (net (code "124") (name "unconnected-(PCB1-PadA2)") (class "Default")
      (node (ref "PCB1") (pin "A2") (pinfunction "A2_A2") (pintype "bidirectional"))
    )
    (net (code "125") (name "unconnected-(PCB1-PadA3)") (class "Default")
      (node (ref "PCB1") (pin "A3") (pinfunction "A3_A3") (pintype "bidirectional"))
    )
    (net (code "126") (name "unconnected-(PCB1-PadA4)") (class "Default")
      (node (ref "PCB1") (pin "A4") (pinfunction "A4_A4") (pintype "bidirectional"))
    )
    (net (code "127") (name "unconnected-(PCB1-PadA5)") (class "Default")
      (node (ref "PCB1") (pin "A5") (pinfunction "A5_A5") (pintype "bidirectional"))
    )
    (net (code "128") (name "unconnected-(PCB1-PadA6)") (class "Default")
      (node (ref "PCB1") (pin "A6") (pinfunction "A6_A6") (pintype "bidirectional"))
    )
    (net (code "129") (name "unconnected-(PCB1-PadA7)") (class "Default")
      (node (ref "PCB1") (pin "A7") (pinfunction "A7_A7") (pintype "bidirectional"))
    )
    (net (code "130") (name "unconnected-(PCB1-PadD2)") (class "Default")
      (node (ref "PCB1") (pin "D2") (pinfunction "D2_D2") (pintype "bidirectional"))
    )
    (net (code "131") (name "unconnected-(PCB1-PadD3)") (class "Default")
      (node (ref "PCB1") (pin "D3") (pinfunction "D3_D3") (pintype "bidirectional"))
    )
    (net (code "132") (name "unconnected-(PCB1-PadD4)") (class "Default")
      (node (ref "PCB1") (pin "D4") (pinfunction "D4_D4") (pintype "bidirectional"))
    )
    (net (code "133") (name "unconnected-(PCB1-PadD13)") (class "Default")
      (node (ref "PCB1") (pin "D13") (pinfunction "D13_D13") (pintype "bidirectional"))
    )
    (net (code "134") (name "unconnected-(PCB1-PadGND)") (class "Default")
      (node (ref "PCB1") (pin "GND") (pinfunction "GND_GND") (pintype "bidirectional"))
    )
    (net (code "135") (name "unconnected-(PCB1-PadGND.)") (class "Default")
      (node (ref "PCB1") (pin "GND.") (pinfunction "GND._GND.") (pintype "bidirectional"))
    )
    (net (code "136") (name "unconnected-(PCB1-PadGND_)") (class "Default")
      (node (ref "PCB1") (pin "GND_") (pinfunction "GND__GND_") (pintype "bidirectional"))
    )
    (net (code "137") (name "unconnected-(PCB1-PadMISO)") (class "Default")
      (node (ref "PCB1") (pin "MISO") (pinfunction "MISO_MISO") (pintype "bidirectional"))
    )
    (net (code "138") (name "unconnected-(PCB1-PadMOSI)") (class "Default")
      (node (ref "PCB1") (pin "MOSI") (pinfunction "MOSI_MOSI") (pintype "bidirectional"))
    )
    (net (code "139") (name "unconnected-(PCB1-PadREF)") (class "Default")
      (node (ref "PCB1") (pin "REF") (pinfunction "REF_REF") (pintype "bidirectional"))
    )
    (net (code "140") (name "unconnected-(PCB1-PadRESET..)") (class "Default")
      (node (ref "PCB1") (pin "RESET..") (pinfunction "RESET.._RESET..") (pintype "bidirectional"))
    )
    (net (code "141") (name "unconnected-(PCB1-PadRST)") (class "Default")
      (node (ref "PCB1") (pin "RST") (pinfunction "RST_RST") (pintype "bidirectional"))
    )
    (net (code "142") (name "unconnected-(PCB1-PadRST.)") (class "Default")
      (node (ref "PCB1") (pin "RST.") (pinfunction "RST._RST.") (pintype "bidirectional"))
    )
    (net (code "143") (name "unconnected-(PCB1-PadSCK)") (class "Default")
      (node (ref "PCB1") (pin "SCK") (pinfunction "SCK_SCK") (pintype "bidirectional"))
    )
    (net (code "144") (name "unconnected-(PCB1-PadTX1)") (class "Default")
      (node (ref "PCB1") (pin "TX1") (pinfunction "TX1_TX1") (pintype "bidirectional"))
    )
    (net (code "145") (name "unconnected-(PCB1-PadVIN)") (class "Default")
      (node (ref "PCB1") (pin "VIN") (pinfunction "VIN_VIN") (pintype "bidirectional"))
    )
    (net (code "146") (name "unconnected-(PCB1-RX0-PadRX1)") (class "Default")
      (node (ref "PCB1") (pin "RX1") (pinfunction "RX0_RX1") (pintype "bidirectional"))
    )
  )
)
